# textool-2-isp.net
KiCad netlist of a schematic drawn in EAGLE
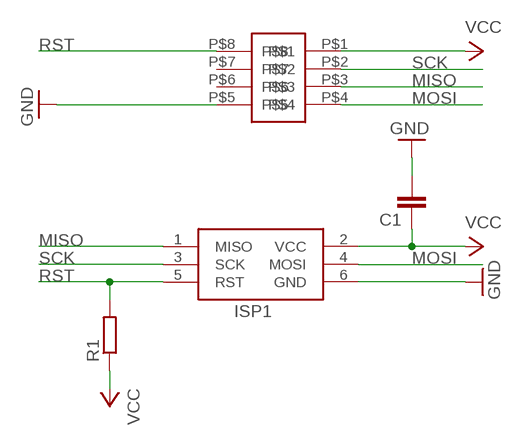
[diagram p0: schematic, sheet 1]

(export (version "E")
  (design (tool "Eeschema 10.0.6"))
  (components
    (comp (ref "C1")
      (value "C-EUC0603")
      (footprint "eagle-import:C0603")
      (libsource (lib "eagle-import") (part "C-EUC0603"))
    )
    (comp (ref "ISP1")
      (value "AVRISP-6")
      (footprint "eagle-import:AVRISP")
      (libsource (lib "eagle-import") (part "AVRISP-6"))
    )
    (comp (ref "R1")
      (value "R-EU_R0603")
      (footprint "eagle-import:R0603")
      (libsource (lib "eagle-import") (part "R-EU_R0603"))
    )
    (comp (ref "U$1")
      (value "TEXTOOL")
      (footprint "eagle-import:TEXTOOL")
      (libsource (lib "eagle-import") (part "TEXTOOL"))
    )
  )
  (nets
    (net (code "1") (name "/MISO") (class "Default")
      (node (ref "ISP1") (pin "1") (pinfunction "MISO_1") (pintype "input"))
      (node (ref "U$1") (pin "P$3") (pinfunction "P$6_P$3") (pintype "bidirectional"))
    )
    (net (code "2") (name "/MOSI") (class "Default")
      (node (ref "ISP1") (pin "4") (pinfunction "MOSI_4") (pintype "output"))
      (node (ref "U$1") (pin "P$4") (pinfunction "P$5_P$4") (pintype "bidirectional"))
    )
    (net (code "3") (name "/RST") (class "Default")
      (node (ref "ISP1") (pin "5") (pinfunction "RST_5") (pintype "output"))
      (node (ref "R1") (pin "2") (pinfunction "2_2") (pintype "passive"))
      (node (ref "U$1") (pin "P$8") (pinfunction "P$1_P$8") (pintype "bidirectional"))
    )
    (net (code "4") (name "/SCK") (class "Default")
      (node (ref "ISP1") (pin "3") (pinfunction "SCK_3") (pintype "output"))
      (node (ref "U$1") (pin "P$2") (pinfunction "P$7_P$2") (pintype "bidirectional"))
    )
    (net (code "5") (name "GND") (class "Default")
      (node (ref "C1") (pin "2") (pinfunction "2_2") (pintype "passive"))
      (node (ref "ISP1") (pin "6") (pinfunction "GND_6") (pintype "power_in"))
      (node (ref "U$1") (pin "P$5") (pinfunction "P$4_P$5") (pintype "bidirectional"))
    )
    (net (code "6") (name "VCC") (class "Default")
      (node (ref "C1") (pin "1") (pinfunction "1_1") (pintype "passive"))
      (node (ref "ISP1") (pin "2") (pinfunction "VCC_2") (pintype "power_in"))
      (node (ref "R1") (pin "1") (pinfunction "1_1") (pintype "passive"))
      (node (ref "U$1") (pin "P$1") (pinfunction "P$8_P$1") (pintype "bidirectional"))
    )
    (net (code "7") (name "unconnected-(U$1-P$2-PadP$7)") (class "Default")
      (node (ref "U$1") (pin "P$7") (pinfunction "P$2_P$7") (pintype "bidirectional"))
    )
    (net (code "8") (name "unconnected-(U$1-P$3-PadP$6)") (class "Default")
      (node (ref "U$1") (pin "P$6") (pinfunction "P$3_P$6") (pintype "bidirectional"))
    )
  )
)
